# tia3.net
KiCad netlist of a schematic drawn in Altium Designer
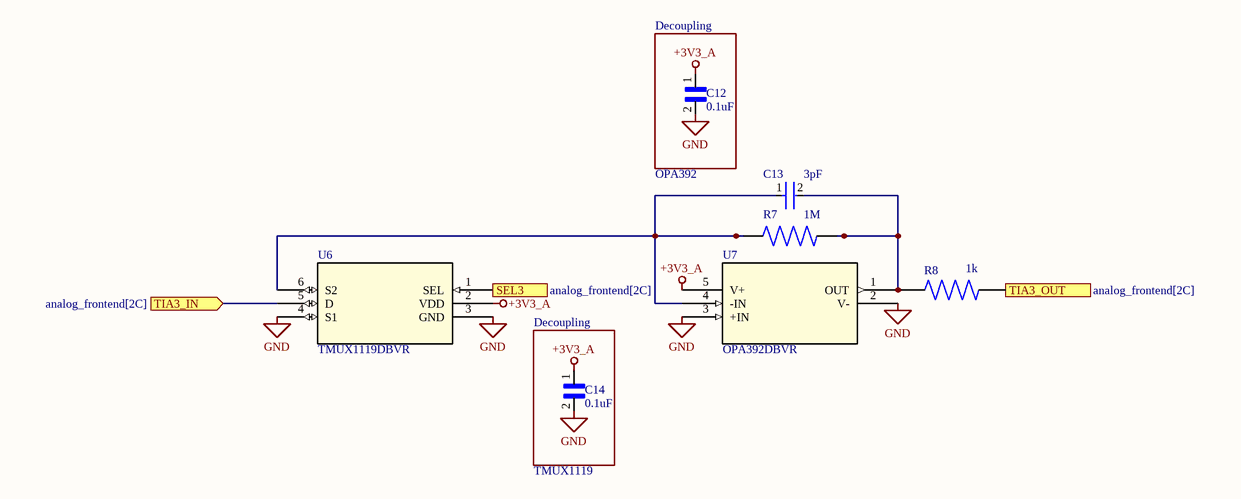
[diagram p0: tia3.SchDoc]

(export (version "E")
  (design (tool "Eeschema 10.0.6"))
  (components
    (comp (ref "C12")
      (value "0.1uF")
      (footprint "CC0603JRX7R8BB104")
      (description "25V 100nF X7R ±5% 0603 Multilayer Ceramic Capacitors MLCC - SMD/SMT ROHS")
      (fields
        (field (name "MANUFACTURER") "Yageo Group")
        (field (name "MANUFACTURER PART NUMBER") "CC0603JRX7R8BB104")
      )
      (libsource (lib "opm_lib") (part "CC0603JRX7R8BB104"))
    )
    (comp (ref "C13")
      (value "3pF")
      (footprint "AQ0603BRNPO9BN3R0")
      (description "Cap, 3Pf, 50V, Mlcc, 0603 Rohs Compliant: Yes ¦Yageo AQ0603BRNPO9BN3R0")
      (fields
        (field (name "MANUFACTURER") "Yageo Group")
        (field (name "MANUFACTURER PART NUMBER") "AQ0603BRNPO9BN3R0")
      )
      (libsource (lib "opm_lib") (part "AQ0603BRNPO9BN3R0"))
    )
    (comp (ref "C14")
      (value "0.1uF")
      (footprint "CC0603JRX7R8BB104")
      (description "25V 100nF X7R ±5% 0603 Multilayer Ceramic Capacitors MLCC - SMD/SMT ROHS")
      (fields
        (field (name "MANUFACTURER") "Yageo Group")
        (field (name "MANUFACTURER PART NUMBER") "CC0603JRX7R8BB104")
      )
      (libsource (lib "opm_lib") (part "CC0603JRX7R8BB104"))
    )
    (comp (ref "R7")
      (value "1M")
      (footprint "RESC2012X55N")
      (description "Res Thin Film 0805 1M Ohm 0.1% 1/8W ±10ppm/°C Molded SMD SMD Paper T/R")
      (fields
        (field (name "MANUFACTURER") "Vishay")
        (field (name "MANUFACTURER PART NUMBER") "TNPW08051M00BYEN")
      )
      (libsource (lib "opm_lib") (part "TNPW08051M00BYEN"))
    )
    (comp (ref "R8")
      (value "1k")
      (footprint "RESC1508X55N")
      (description "Fixed Resistor, Thin Film, 0.1W, 1000ohm, 75V, 0.1% +/-Tol, 15ppm/Cel, Surface Mount, 0603")
      (fields
        (field (name "MANUFACTURER") "Vishay")
        (field (name "MANUFACTURER PART NUMBER") "TNPW06031K00BXEN")
      )
      (libsource (lib "opm_lib") (part "TNPW06031K00BXEN"))
    )
    (comp (ref "U6")
      (value "TMUX1119DBVR")
      (footprint "TMUX1119DBVR")
      (fields (field (name "MANUFACTURER") "Texas Instruments"))
      (libsource (lib "opm_lib") (part "TMUX1119DBVR"))
    )
    (comp (ref "U7")
      (value "OPA392DBVR")
      (footprint "OPA392DBVR")
      (description "Operational Amplifier, 1 Func, 10uV Offset-Max, CMOS, PDSO5")
      (fields (field (name "MANUFACTURER") "Texas Instruments"))
      (libsource (lib "opm_lib") (part "OPA392DBVR"))
    )
  )
  (nets
    (net (code "1") (name "+3V3_A") (class "Default")
      (node (ref "C12") (pin "1") (pinfunction "1_1") (pintype "passive"))
      (node (ref "C14") (pin "1") (pinfunction "1_1") (pintype "passive"))
      (node (ref "U6") (pin "2") (pinfunction "VDD_2") (pintype "power_in"))
      (node (ref "U7") (pin "5") (pinfunction "V+_5") (pintype "power_in"))
    )
    (net (code "2") (name "/SEL3") (class "Default")
      (node (ref "U6") (pin "1") (pinfunction "SEL_1") (pintype "input"))
    )
    (net (code "3") (name "/TIA3_IN") (class "Default")
      (node (ref "U6") (pin "5") (pinfunction "D_5") (pintype "bidirectional"))
    )
    (net (code "4") (name "/TIA3_OUT") (class "Default")
      (node (ref "R8") (pin "2") (pinfunction "2_2") (pintype "passive"))
    )
    (net (code "5") (name "GND") (class "Default")
      (node (ref "C12") (pin "2") (pinfunction "2_2") (pintype "passive"))
      (node (ref "C14") (pin "2") (pinfunction "2_2") (pintype "passive"))
      (node (ref "U6") (pin "3") (pinfunction "GND_3") (pintype "power_in"))
      (node (ref "U6") (pin "4") (pinfunction "S1_4") (pintype "bidirectional"))
      (node (ref "U7") (pin "2") (pinfunction "V-_2") (pintype "power_in"))
      (node (ref "U7") (pin "3") (pinfunction "+IN_3") (pintype "input"))
    )
    (net (code "6") (name "Net-(U6-S2)") (class "Default")
      (node (ref "C13") (pin "1") (pinfunction "1_1") (pintype "passive"))
      (node (ref "R7") (pin "1") (pinfunction "1_1") (pintype "passive"))
      (node (ref "U6") (pin "6") (pinfunction "S2_6") (pintype "bidirectional"))
      (node (ref "U7") (pin "4") (pinfunction "-IN_4") (pintype "input"))
    )
    (net (code "7") (name "Net-(U7-OUT)") (class "Default")
      (node (ref "C13") (pin "2") (pinfunction "2_2") (pintype "passive"))
      (node (ref "R7") (pin "2") (pinfunction "2_2") (pintype "passive"))
      (node (ref "R8") (pin "1") (pinfunction "1_1") (pintype "passive"))
      (node (ref "U7") (pin "1") (pinfunction "OUT_1") (pintype "output"))
    )
  )
)
